# keyboardV0_1.net
KiCad netlist of a schematic drawn in Altium Designer
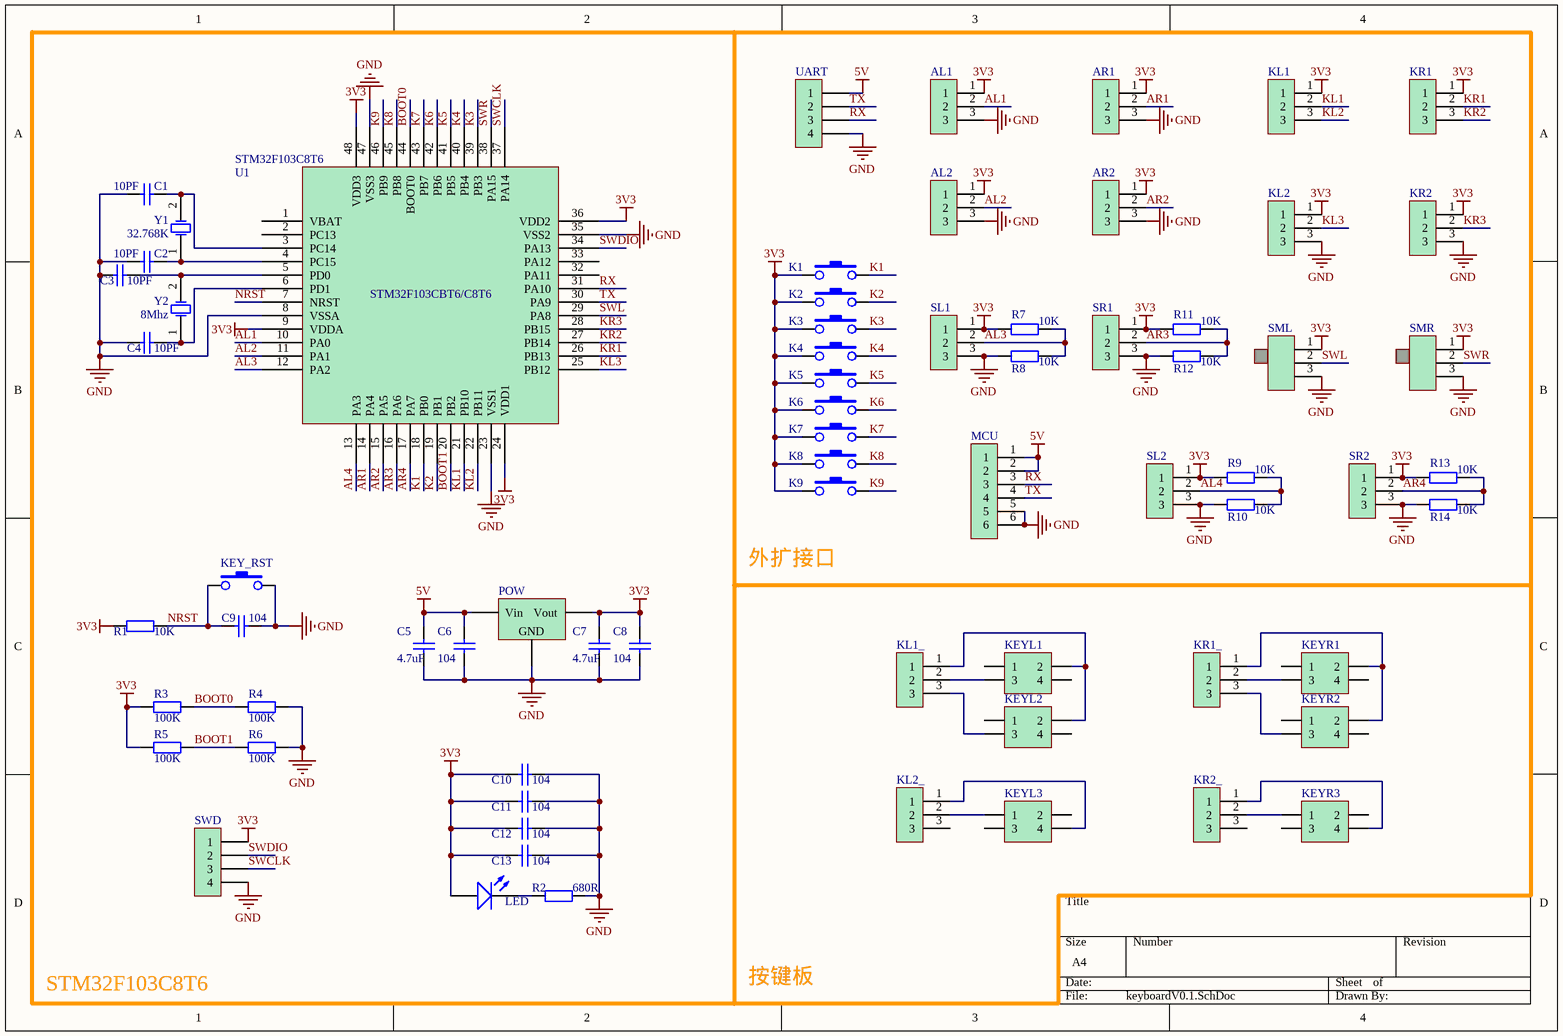
[diagram p0: keyboardV0.1.SchDoc]

(export (version "E")
  (design (tool "Eeschema 10.0.6"))
  (components
    (comp (ref "AL1")
      (value "SH1.25mm_3P")
      (footprint "SH1.25mm_3P")
      (libsource (lib "MT_Connector") (part "SH1.25mm_3P"))
    )
    (comp (ref "AL2")
      (value "SH1.25mm_3P")
      (footprint "SH1.25mm_3P")
      (libsource (lib "MT_Connector") (part "SH1.25mm_3P"))
    )
    (comp (ref "AR1")
      (value "SH1.25mm_3P")
      (footprint "SH1.25mm_3P")
      (libsource (lib "MT_Connector") (part "SH1.25mm_3P"))
    )
    (comp (ref "AR2")
      (value "SH1.25mm_3P")
      (footprint "SH1.25mm_3P")
      (libsource (lib "MT_Connector") (part "SH1.25mm_3P"))
    )
    (comp (ref "C1") (value "10PF") (footprint "0603_C") (libsource (lib "MT_Device") (part "0603_CAP")))
    (comp (ref "C2") (value "10PF") (footprint "0603_C") (libsource (lib "MT_Device") (part "0603_CAP")))
    (comp (ref "C3") (value "10PF") (footprint "0603_C") (libsource (lib "MT_Device") (part "0603_CAP")))
    (comp (ref "C4") (value "10PF") (footprint "0603_C") (libsource (lib "MT_Device") (part "0603_CAP")))
    (comp (ref "C5") (value "4.7uF") (footprint "0603_C") (libsource (lib "MT_Device") (part "0603_CAP")))
    (comp (ref "C6") (value "104") (footprint "0603_C") (libsource (lib "MT_Device") (part "0603_CAP")))
    (comp (ref "C7") (value "4.7uF") (footprint "0603_C") (libsource (lib "MT_Device") (part "0603_CAP")))
    (comp (ref "C8") (value "104") (footprint "0603_C") (libsource (lib "MT_Device") (part "0603_CAP")))
    (comp (ref "C9") (value "104") (footprint "0603_C") (libsource (lib "MT_Device") (part "0603_CAP")))
    (comp (ref "C10") (value "104") (footprint "0603_C") (libsource (lib "MT_Device") (part "0603_CAP")))
    (comp (ref "C11") (value "104") (footprint "0603_C") (libsource (lib "MT_Device") (part "0603_CAP")))
    (comp (ref "C12") (value "104") (footprint "0603_C") (libsource (lib "MT_Device") (part "0603_CAP")))
    (comp (ref "C13") (value "104") (footprint "0603_C") (libsource (lib "MT_Device") (part "0603_CAP")))
    (comp (ref "K1")
      (value "KEY_S_6*6")
      (footprint "KEY_S_6*6")
      (libsource (lib "MT_Device") (part "KEY_S_6*6"))
    )
    (comp (ref "K2")
      (value "KEY_S_6*6")
      (footprint "KEY_S_6*6")
      (libsource (lib "MT_Device") (part "KEY_S_6*6"))
    )
    (comp (ref "K3")
      (value "KEY_S_6*6")
      (footprint "KEY_S_6*6")
      (libsource (lib "MT_Device") (part "KEY_S_6*6"))
    )
    (comp (ref "K4")
      (value "KEY_S_6*6")
      (footprint "KEY_S_6*6")
      (libsource (lib "MT_Device") (part "KEY_S_6*6"))
    )
    (comp (ref "K5")
      (value "KEY_S_6*6")
      (footprint "KEY_S_6*6")
      (libsource (lib "MT_Device") (part "KEY_S_6*6"))
    )
    (comp (ref "K6")
      (value "KEY_S_6*6")
      (footprint "KEY_S_6*6")
      (libsource (lib "MT_Device") (part "KEY_S_6*6"))
    )
    (comp (ref "K7")
      (value "KEY_S_6*6")
      (footprint "KEY_S_6*6")
      (libsource (lib "MT_Device") (part "KEY_S_6*6"))
    )
    (comp (ref "K8")
      (value "KEY_S_6*6")
      (footprint "KEY_S_6*6")
      (libsource (lib "MT_Device") (part "KEY_S_6*6"))
    )
    (comp (ref "K9")
      (value "KEY_S_6*6")
      (footprint "KEY_S_6*6")
      (libsource (lib "MT_Device") (part "KEY_S_6*6"))
    )
    (comp (ref "KEYL1") (value "KEY") (footprint "KEY_6*6") (libsource (lib "MT_Device") (part "KEY_6*6")))
    (comp (ref "KEYL2") (value "KEY") (footprint "KEY_6*6") (libsource (lib "MT_Device") (part "KEY_6*6")))
    (comp (ref "KEYL3") (value "KEY") (footprint "KEY_6*6") (libsource (lib "MT_Device") (part "KEY_6*6")))
    (comp (ref "KEYR1") (value "KEY") (footprint "KEY_6*6") (libsource (lib "MT_Device") (part "KEY_6*6")))
    (comp (ref "KEYR2") (value "KEY") (footprint "KEY_6*6") (libsource (lib "MT_Device") (part "KEY_6*6")))
    (comp (ref "KEYR3") (value "KEY") (footprint "KEY_6*6") (libsource (lib "MT_Device") (part "KEY_6*6")))
    (comp (ref "KEY_RST")
      (value "KEY_SMT")
      (footprint "KEY_SMT")
      (libsource (lib "MT_Device") (part "KEY_SMT"))
    )
    (comp (ref "KL1")
      (value "SH1.25mm_3P")
      (footprint "SH1.25mm_3P")
      (libsource (lib "MT_Connector") (part "SH1.25mm_3P"))
    )
    (comp (ref "KL1_")
      (value "SH1.25mm_3P")
      (footprint "SH1.25mm_3P")
      (libsource (lib "MT_Connector") (part "SH1.25mm_3P"))
    )
    (comp (ref "KL2")
      (value "SH1.25mm_3P")
      (footprint "SH1.25mm_3P")
      (libsource (lib "MT_Connector") (part "SH1.25mm_3P"))
    )
    (comp (ref "KL2_")
      (value "SH1.25mm_3P")
      (footprint "SH1.25mm_3P")
      (libsource (lib "MT_Connector") (part "SH1.25mm_3P"))
    )
    (comp (ref "KR1")
      (value "SH1.25mm_3P")
      (footprint "SH1.25mm_3P")
      (libsource (lib "MT_Connector") (part "SH1.25mm_3P"))
    )
    (comp (ref "KR1_")
      (value "SH1.25mm_3P")
      (footprint "SH1.25mm_3P")
      (libsource (lib "MT_Connector") (part "SH1.25mm_3P"))
    )
    (comp (ref "KR2")
      (value "SH1.25mm_3P")
      (footprint "SH1.25mm_3P")
      (libsource (lib "MT_Connector") (part "SH1.25mm_3P"))
    )
    (comp (ref "KR2_")
      (value "SH1.25mm_3P")
      (footprint "SH1.25mm_3P")
      (libsource (lib "MT_Connector") (part "SH1.25mm_3P"))
    )
    (comp (ref "LED")
      (value "0603_LED")
      (footprint "0603_LED")
      (libsource (lib "MT_Device") (part "0603_LED"))
    )
    (comp (ref "MCU")
      (value "SH1.25mm_6P")
      (footprint "SH1.25MM_6P")
      (libsource (lib "MT_Connector") (part "SH1.25mm_6P"))
    )
    (comp (ref "POW")
      (value "AMS1117_3.3")
      (footprint "SOT223")
      (libsource (lib "MT_Device") (part "AMS1117_3.3"))
    )
    (comp (ref "R1") (value "10K") (footprint "0603_R") (libsource (lib "") (part "0603_RES_1")))
    (comp (ref "R2") (value "680R") (footprint "0603_R") (libsource (lib "") (part "0603_RES_1")))
    (comp (ref "R3") (value "100K") (footprint "0603_R") (libsource (lib "MT_Device") (part "0603_RES")))
    (comp (ref "R4") (value "100K") (footprint "0603_R") (libsource (lib "MT_Device") (part "0603_RES")))
    (comp (ref "R5") (value "100K") (footprint "0603_R") (libsource (lib "MT_Device") (part "0603_RES")))
    (comp (ref "R6") (value "100K") (footprint "0603_R") (libsource (lib "MT_Device") (part "0603_RES")))
    (comp (ref "R7") (value "10K") (footprint "0603_R") (libsource (lib "MT_Device") (part "0603_RES")))
    (comp (ref "R8") (value "10K") (footprint "0603_R") (libsource (lib "MT_Device") (part "0603_RES")))
    (comp (ref "R9") (value "10K") (footprint "0603_R") (libsource (lib "MT_Device") (part "0603_RES")))
    (comp (ref "R10") (value "10K") (footprint "0603_R") (libsource (lib "MT_Device") (part "0603_RES")))
    (comp (ref "R11") (value "10K") (footprint "0603_R") (libsource (lib "MT_Device") (part "0603_RES")))
    (comp (ref "R12") (value "10K") (footprint "0603_R") (libsource (lib "MT_Device") (part "0603_RES")))
    (comp (ref "R13") (value "10K") (footprint "0603_R") (libsource (lib "MT_Device") (part "0603_RES")))
    (comp (ref "R14") (value "10K") (footprint "0603_R") (libsource (lib "MT_Device") (part "0603_RES")))
    (comp (ref "SL1")
      (value "SH1.25mm_3P")
      (footprint "SH1.25mm_3P")
      (libsource (lib "MT_Connector") (part "SH1.25mm_3P"))
    )
    (comp (ref "SL2")
      (value "SH1.25mm_3P")
      (footprint "SH1.25mm_3P")
      (libsource (lib "MT_Connector") (part "SH1.25mm_3P"))
    )
    (comp (ref "SML")
      (value "SWITCH")
      (footprint "SWITCH_SS12F44")
      (libsource (lib "MT_Device") (part "SWITCH_SS12F44"))
    )
    (comp (ref "SMR")
      (value "SWITCH")
      (footprint "SWITCH_SS12F44")
      (libsource (lib "MT_Device") (part "SWITCH_SS12F44"))
    )
    (comp (ref "SR1")
      (value "SH1.25mm_3P")
      (footprint "SH1.25mm_3P")
      (libsource (lib "MT_Connector") (part "SH1.25mm_3P"))
    )
    (comp (ref "SR2")
      (value "SH1.25mm_3P")
      (footprint "SH1.25mm_3P")
      (libsource (lib "MT_Connector") (part "SH1.25mm_3P"))
    )
    (comp (ref "SWD")
      (value "Header_2.54_4P")
      (footprint "HDR1_4P")
      (libsource (lib "MT_Connector") (part "Header_2.54_4P"))
    )
    (comp (ref "U1")
      (value "STM32F103C8T6")
      (footprint "LQFP48")
      (libsource (lib "MT_Chip") (part "STM32F103C8T6"))
    )
    (comp (ref "UART")
      (value "Header_2.54_4P")
      (footprint "HDR1_4P")
      (libsource (lib "MT_Connector") (part "Header_2.54_4P"))
    )
    (comp (ref "Y1")
      (value "32.768K")
      (footprint "XTAL_32.768_3215_2")
      (libsource (lib "MT_Device") (part "XTAL_32.768_3215_2"))
    )
    (comp (ref "Y2")
      (value "8Mhz")
      (footprint "XTAL_5032_2")
      (libsource (lib "MT_Device") (part "XTAL_8MHz_5032_2"))
    )
  )
  (nets
    (net (code "1") (name "/AL1") (class "Default")
      (node (ref "AL1") (pin "2") (pinfunction "2_2") (pintype "passive"))
      (node (ref "U1") (pin "10") (pinfunction "PA0_10") (pintype "passive"))
    )
    (net (code "2") (name "/AL2") (class "Default")
      (node (ref "AL2") (pin "2") (pinfunction "2_2") (pintype "passive"))
      (node (ref "U1") (pin "11") (pinfunction "PA1_11") (pintype "passive"))
    )
    (net (code "3") (name "/AL3") (class "Default")
      (node (ref "R7") (pin "1") (pinfunction "1_1") (pintype "passive"))
      (node (ref "R8") (pin "1") (pinfunction "1_1") (pintype "passive"))
      (node (ref "SL1") (pin "2") (pinfunction "2_2") (pintype "passive"))
      (node (ref "U1") (pin "12") (pinfunction "PA2_12") (pintype "passive"))
    )
    (net (code "4") (name "/AL4") (class "Default")
      (node (ref "R10") (pin "1") (pinfunction "1_1") (pintype "passive"))
      (node (ref "R9") (pin "1") (pinfunction "1_1") (pintype "passive"))
      (node (ref "SL2") (pin "2") (pinfunction "2_2") (pintype "passive"))
      (node (ref "U1") (pin "13") (pinfunction "PA3_13") (pintype "passive"))
    )
    (net (code "5") (name "/AR1") (class "Default")
      (node (ref "AR1") (pin "2") (pinfunction "2_2") (pintype "passive"))
      (node (ref "U1") (pin "14") (pinfunction "PA4_14") (pintype "passive"))
    )
    (net (code "6") (name "/AR2") (class "Default")
      (node (ref "AR2") (pin "2") (pinfunction "2_2") (pintype "passive"))
      (node (ref "U1") (pin "15") (pinfunction "PA5_15") (pintype "passive"))
    )
    (net (code "7") (name "/AR3") (class "Default")
      (node (ref "R11") (pin "1") (pinfunction "1_1") (pintype "passive"))
      (node (ref "R12") (pin "1") (pinfunction "1_1") (pintype "passive"))
      (node (ref "SR1") (pin "2") (pinfunction "2_2") (pintype "passive"))
      (node (ref "U1") (pin "16") (pinfunction "PA6_16") (pintype "passive"))
    )
    (net (code "8") (name "/AR4") (class "Default")
      (node (ref "R13") (pin "1") (pinfunction "1_1") (pintype "passive"))
      (node (ref "R14") (pin "1") (pinfunction "1_1") (pintype "passive"))
      (node (ref "SR2") (pin "2") (pinfunction "2_2") (pintype "passive"))
      (node (ref "U1") (pin "17") (pinfunction "PA7_17") (pintype "passive"))
    )
    (net (code "9") (name "/BOOT0") (class "Default")
      (node (ref "R3") (pin "1") (pinfunction "1_1") (pintype "passive"))
      (node (ref "R4") (pin "2") (pinfunction "2_2") (pintype "passive"))
      (node (ref "U1") (pin "44") (pinfunction "BOOT0_44") (pintype "passive"))
    )
    (net (code "10") (name "/BOOT1") (class "Default")
      (node (ref "R5") (pin "1") (pinfunction "1_1") (pintype "passive"))
      (node (ref "R6") (pin "2") (pinfunction "2_2") (pintype "passive"))
      (node (ref "U1") (pin "20") (pinfunction "PB2_20") (pintype "passive"))
    )
    (net (code "11") (name "/K1") (class "Default")
      (node (ref "K1") (pin "2") (pinfunction "2_2") (pintype "passive"))
      (node (ref "U1") (pin "18") (pinfunction "PB0_18") (pintype "passive"))
    )
    (net (code "12") (name "/K2") (class "Default")
      (node (ref "K2") (pin "2") (pinfunction "2_2") (pintype "passive"))
      (node (ref "U1") (pin "19") (pinfunction "PB1_19") (pintype "passive"))
    )
    (net (code "13") (name "/K3") (class "Default")
      (node (ref "K3") (pin "2") (pinfunction "2_2") (pintype "passive"))
      (node (ref "U1") (pin "39") (pinfunction "PB3_39") (pintype "passive"))
    )
    (net (code "14") (name "/K4") (class "Default")
      (node (ref "K4") (pin "2") (pinfunction "2_2") (pintype "passive"))
      (node (ref "U1") (pin "40") (pinfunction "PB4_40") (pintype "passive"))
    )
    (net (code "15") (name "/K5") (class "Default")
      (node (ref "K5") (pin "2") (pinfunction "2_2") (pintype "passive"))
      (node (ref "U1") (pin "41") (pinfunction "PB5_41") (pintype "passive"))
    )
    (net (code "16") (name "/K6") (class "Default")
      (node (ref "K6") (pin "2") (pinfunction "2_2") (pintype "passive"))
      (node (ref "U1") (pin "42") (pinfunction "PB6_42") (pintype "passive"))
    )
    (net (code "17") (name "/K7") (class "Default")
      (node (ref "K7") (pin "2") (pinfunction "2_2") (pintype "passive"))
      (node (ref "U1") (pin "43") (pinfunction "PB7_43") (pintype "passive"))
    )
    (net (code "18") (name "/K8") (class "Default")
      (node (ref "K8") (pin "2") (pinfunction "2_2") (pintype "passive"))
      (node (ref "U1") (pin "45") (pinfunction "PB8_45") (pintype "passive"))
    )
    (net (code "19") (name "/K9") (class "Default")
      (node (ref "K9") (pin "2") (pinfunction "2_2") (pintype "passive"))
      (node (ref "U1") (pin "46") (pinfunction "PB9_46") (pintype "passive"))
    )
    (net (code "20") (name "/KL1") (class "Default")
      (node (ref "KL1") (pin "2") (pinfunction "2_2") (pintype "passive"))
      (node (ref "U1") (pin "21") (pinfunction "PB10_21") (pintype "passive"))
    )
    (net (code "21") (name "/KL2") (class "Default")
      (node (ref "KL1") (pin "3") (pinfunction "3_3") (pintype "passive"))
      (node (ref "U1") (pin "22") (pinfunction "PB11_22") (pintype "passive"))
    )
    (net (code "22") (name "/KL3") (class "Default")
      (node (ref "KL2") (pin "2") (pinfunction "2_2") (pintype "passive"))
      (node (ref "U1") (pin "25") (pinfunction "PB12_25") (pintype "passive"))
    )
    (net (code "23") (name "/KR1") (class "Default")
      (node (ref "KR1") (pin "2") (pinfunction "2_2") (pintype "passive"))
      (node (ref "U1") (pin "26") (pinfunction "PB13_26") (pintype "passive"))
    )
    (net (code "24") (name "/KR2") (class "Default")
      (node (ref "KR1") (pin "3") (pinfunction "3_3") (pintype "passive"))
      (node (ref "U1") (pin "27") (pinfunction "PB14_27") (pintype "passive"))
    )
    (net (code "25") (name "/KR3") (class "Default")
      (node (ref "KR2") (pin "2") (pinfunction "2_2") (pintype "passive"))
      (node (ref "U1") (pin "28") (pinfunction "PB15_28") (pintype "passive"))
    )
    (net (code "26") (name "/NRST") (class "Default")
      (node (ref "C9") (pin "2") (pinfunction "2_2") (pintype "passive"))
      (node (ref "KEY_RST") (pin "1") (pinfunction "1_1") (pintype "passive"))
      (node (ref "R1") (pin "2") (pinfunction "2_2") (pintype "passive"))
      (node (ref "U1") (pin "7") (pinfunction "NRST_7") (pintype "passive"))
    )
    (net (code "27") (name "/RX") (class "Default")
      (node (ref "MCU") (pin "3") (pinfunction "3_3") (pintype "passive"))
      (node (ref "U1") (pin "31") (pinfunction "PA10_31") (pintype "passive"))
      (node (ref "UART") (pin "3") (pinfunction "3_3") (pintype "passive"))
    )
    (net (code "28") (name "/SWCLK") (class "Default")
      (node (ref "SWD") (pin "3") (pinfunction "3_3") (pintype "passive"))
      (node (ref "U1") (pin "37") (pinfunction "PA14_37") (pintype "passive"))
    )
    (net (code "29") (name "/SWDIO") (class "Default")
      (node (ref "SWD") (pin "2") (pinfunction "2_2") (pintype "passive"))
      (node (ref "U1") (pin "34") (pinfunction "PA13_34") (pintype "passive"))
    )
    (net (code "30") (name "/SWL") (class "Default")
      (node (ref "SML") (pin "2") (pinfunction "2_2") (pintype "passive"))
      (node (ref "U1") (pin "29") (pinfunction "PA8_29") (pintype "passive"))
    )
    (net (code "31") (name "/SWR") (class "Default")
      (node (ref "SMR") (pin "2") (pinfunction "2_2") (pintype "passive"))
      (node (ref "U1") (pin "38") (pinfunction "PA15_38") (pintype "passive"))
    )
    (net (code "32") (name "/TX") (class "Default")
      (node (ref "MCU") (pin "4") (pinfunction "4_4") (pintype "passive"))
      (node (ref "U1") (pin "30") (pinfunction "PA9_30") (pintype "passive"))
      (node (ref "UART") (pin "2") (pinfunction "2_2") (pintype "passive"))
    )
    (net (code "33") (name "3V3") (class "Default")
      (node (ref "AL1") (pin "1") (pinfunction "1_1") (pintype "passive"))
      (node (ref "AL2") (pin "1") (pinfunction "1_1") (pintype "passive"))
      (node (ref "AR1") (pin "1") (pinfunction "1_1") (pintype "passive"))
      (node (ref "AR2") (pin "1") (pinfunction "1_1") (pintype "passive"))
      (node (ref "C10") (pin "2") (pinfunction "2_2") (pintype "passive"))
      (node (ref "C11") (pin "2") (pinfunction "2_2") (pintype "passive"))
      (node (ref "C12") (pin "2") (pinfunction "2_2") (pintype "passive"))
      (node (ref "C13") (pin "2") (pinfunction "2_2") (pintype "passive"))
      (node (ref "C7") (pin "1") (pinfunction "1_1") (pintype "passive"))
      (node (ref "C8") (pin "1") (pinfunction "1_1") (pintype "passive"))
      (node (ref "K1") (pin "1") (pinfunction "1_1") (pintype "passive"))
      (node (ref "K2") (pin "1") (pinfunction "1_1") (pintype "passive"))
      (node (ref "K3") (pin "1") (pinfunction "1_1") (pintype "passive"))
      (node (ref "K4") (pin "1") (pinfunction "1_1") (pintype "passive"))
      (node (ref "K5") (pin "1") (pinfunction "1_1") (pintype "passive"))
      (node (ref "K6") (pin "1") (pinfunction "1_1") (pintype "passive"))
      (node (ref "K7") (pin "1") (pinfunction "1_1") (pintype "passive"))
      (node (ref "K8") (pin "1") (pinfunction "1_1") (pintype "passive"))
      (node (ref "K9") (pin "1") (pinfunction "1_1") (pintype "passive"))
      (node (ref "KL1") (pin "1") (pinfunction "1_1") (pintype "passive"))
      (node (ref "KL2") (pin "1") (pinfunction "1_1") (pintype "passive"))
      (node (ref "KR1") (pin "1") (pinfunction "1_1") (pintype "passive"))
      (node (ref "KR2") (pin "1") (pinfunction "1_1") (pintype "passive"))
      (node (ref "LED") (pin "A") (pinfunction "A_A") (pintype "passive"))
      (node (ref "POW") (pin "2") (pinfunction "Vout_2") (pintype "passive"))
      (node (ref "R1") (pin "1") (pinfunction "1_1") (pintype "passive"))
      (node (ref "R11") (pin "2") (pinfunction "2_2") (pintype "passive"))
      (node (ref "R13") (pin "2") (pinfunction "2_2") (pintype "passive"))
      (node (ref "R3") (pin "2") (pinfunction "2_2") (pintype "passive"))
      (node (ref "R5") (pin "2") (pinfunction "2_2") (pintype "passive"))
      (node (ref "R7") (pin "2") (pinfunction "2_2") (pintype "passive"))
      (node (ref "R9") (pin "2") (pinfunction "2_2") (pintype "passive"))
      (node (ref "SL1") (pin "1") (pinfunction "1_1") (pintype "passive"))
      (node (ref "SL2") (pin "1") (pinfunction "1_1") (pintype "passive"))
      (node (ref "SML") (pin "1") (pinfunction "1_1") (pintype "passive"))
      (node (ref "SMR") (pin "1") (pinfunction "1_1") (pintype "passive"))
      (node (ref "SR1") (pin "1") (pinfunction "1_1") (pintype "passive"))
      (node (ref "SR2") (pin "1") (pinfunction "1_1") (pintype "passive"))
      (node (ref "SWD") (pin "1") (pinfunction "1_1") (pintype "passive"))
      (node (ref "U1") (pin "24") (pinfunction "VDD1_24") (pintype "passive"))
      (node (ref "U1") (pin "36") (pinfunction "VDD2_36") (pintype "passive"))
      (node (ref "U1") (pin "48") (pinfunction "VDD3_48") (pintype "passive"))
      (node (ref "U1") (pin "9") (pinfunction "VDDA_9") (pintype "passive"))
    )
    (net (code "34") (name "5V") (class "Default")
      (node (ref "C5") (pin "1") (pinfunction "1_1") (pintype "passive"))
      (node (ref "C6") (pin "1") (pinfunction "1_1") (pintype "passive"))
      (node (ref "MCU") (pin "1") (pinfunction "1_1") (pintype "passive"))
      (node (ref "MCU") (pin "2") (pinfunction "2_2") (pintype "passive"))
      (node (ref "POW") (pin "3") (pinfunction "Vin_3") (pintype "passive"))
      (node (ref "UART") (pin "1") (pinfunction "1_1") (pintype "passive"))
    )
    (net (code "35") (name "GND") (class "Default")
      (node (ref "AL1") (pin "3") (pinfunction "3_3") (pintype "passive"))
      (node (ref "AL2") (pin "3") (pinfunction "3_3") (pintype "passive"))
      (node (ref "AR1") (pin "3") (pinfunction "3_3") (pintype "passive"))
      (node (ref "AR2") (pin "3") (pinfunction "3_3") (pintype "passive"))
      (node (ref "C1") (pin "1") (pinfunction "1_1") (pintype "passive"))
      (node (ref "C10") (pin "1") (pinfunction "1_1") (pintype "passive"))
      (node (ref "C11") (pin "1") (pinfunction "1_1") (pintype "passive"))
      (node (ref "C12") (pin "1") (pinfunction "1_1") (pintype "passive"))
      (node (ref "C13") (pin "1") (pinfunction "1_1") (pintype "passive"))
      (node (ref "C2") (pin "1") (pinfunction "1_1") (pintype "passive"))
      (node (ref "C3") (pin "1") (pinfunction "1_1") (pintype "passive"))
      (node (ref "C4") (pin "1") (pinfunction "1_1") (pintype "passive"))
      (node (ref "C5") (pin "2") (pinfunction "2_2") (pintype "passive"))
      (node (ref "C6") (pin "2") (pinfunction "2_2") (pintype "passive"))
      (node (ref "C7") (pin "2") (pinfunction "2_2") (pintype "passive"))
      (node (ref "C8") (pin "2") (pinfunction "2_2") (pintype "passive"))
      (node (ref "C9") (pin "1") (pinfunction "1_1") (pintype "passive"))
      (node (ref "KEY_RST") (pin "2") (pinfunction "2_2") (pintype "passive"))
      (node (ref "KL2") (pin "3") (pinfunction "3_3") (pintype "passive"))
      (node (ref "KR2") (pin "3") (pinfunction "3_3") (pintype "passive"))
      (node (ref "MCU") (pin "5") (pinfunction "5_5") (pintype "passive"))
      (node (ref "MCU") (pin "6") (pinfunction "6_6") (pintype "passive"))
      (node (ref "POW") (pin "1") (pinfunction "GND_1") (pintype "passive"))
      (node (ref "R10") (pin "2") (pinfunction "2_2") (pintype "passive"))
      (node (ref "R12") (pin "2") (pinfunction "2_2") (pintype "passive"))
      (node (ref "R14") (pin "2") (pinfunction "2_2") (pintype "passive"))
      (node (ref "R2") (pin "2") (pinfunction "2_2") (pintype "passive"))
      (node (ref "R4") (pin "1") (pinfunction "1_1") (pintype "passive"))
      (node (ref "R6") (pin "1") (pinfunction "1_1") (pintype "passive"))
      (node (ref "R8") (pin "2") (pinfunction "2_2") (pintype "passive"))
      (node (ref "SL1") (pin "3") (pinfunction "3_3") (pintype "passive"))
      (node (ref "SL2") (pin "3") (pinfunction "3_3") (pintype "passive"))
      (node (ref "SML") (pin "3") (pinfunction "3_3") (pintype "passive"))
      (node (ref "SMR") (pin "3") (pinfunction "3_3") (pintype "passive"))
      (node (ref "SR1") (pin "3") (pinfunction "3_3") (pintype "passive"))
      (node (ref "SR2") (pin "3") (pinfunction "3_3") (pintype "passive"))
      (node (ref "SWD") (pin "4") (pinfunction "4_4") (pintype "passive"))
      (node (ref "U1") (pin "23") (pinfunction "VSS1_23") (pintype "passive"))
      (node (ref "U1") (pin "35") (pinfunction "VSS2_35") (pintype "passive"))
      (node (ref "U1") (pin "47") (pinfunction "VSS3_47") (pintype "passive"))
      (node (ref "U1") (pin "8") (pinfunction "VSSA_8") (pintype "passive"))
      (node (ref "UART") (pin "4") (pinfunction "4_4") (pintype "passive"))
    )
    (net (code "36") (name "Net-(KEYL1-Pad2)") (class "Default")
      (node (ref "KEYL1") (pin "2") (pinfunction "2_2") (pintype "passive"))
      (node (ref "KEYL2") (pin "2") (pinfunction "2_2") (pintype "passive"))
      (node (ref "KL1_") (pin "1") (pinfunction "1_1") (pintype "passive"))
    )
    (net (code "37") (name "Net-(KEYL1-Pad3)") (class "Default")
      (node (ref "KEYL1") (pin "3") (pinfunction "3_3") (pintype "passive"))
      (node (ref "KL1_") (pin "2") (pinfunction "2_2") (pintype "passive"))
    )
    (net (code "38") (name "Net-(KEYL2-Pad3)") (class "Default")
      (node (ref "KEYL2") (pin "3") (pinfunction "3_3") (pintype "passive"))
      (node (ref "KL1_") (pin "3") (pinfunction "3_3") (pintype "passive"))
    )
    (net (code "39") (name "Net-(KEYL3-Pad1)") (class "Default")
      (node (ref "KEYL3") (pin "1") (pinfunction "1_1") (pintype "passive"))
      (node (ref "KL2_") (pin "2") (pinfunction "2_2") (pintype "passive"))
    )
    (net (code "40") (name "Net-(KEYL3-Pad4)") (class "Default")
      (node (ref "KEYL3") (pin "4") (pinfunction "4_4") (pintype "passive"))
      (node (ref "KL2_") (pin "1") (pinfunction "1_1") (pintype "passive"))
    )
    (net (code "41") (name "Net-(KEYR1-Pad2)") (class "Default")
      (node (ref "KEYR1") (pin "2") (pinfunction "2_2") (pintype "passive"))
      (node (ref "KEYR2") (pin "2") (pinfunction "2_2") (pintype "passive"))
      (node (ref "KR1_") (pin "1") (pinfunction "1_1") (pintype "passive"))
    )
    (net (code "42") (name "Net-(KEYR1-Pad3)") (class "Default")
      (node (ref "KEYR1") (pin "3") (pinfunction "3_3") (pintype "passive"))
      (node (ref "KR1_") (pin "2") (pinfunction "2_2") (pintype "passive"))
    )
    (net (code "43") (name "Net-(KEYR2-Pad3)") (class "Default")
      (node (ref "KEYR2") (pin "3") (pinfunction "3_3") (pintype "passive"))
      (node (ref "KR1_") (pin "3") (pinfunction "3_3") (pintype "passive"))
    )
    (net (code "44") (name "Net-(KEYR3-Pad1)") (class "Default")
      (node (ref "KEYR3") (pin "1") (pinfunction "1_1") (pintype "passive"))
      (node (ref "KR2_") (pin "2") (pinfunction "2_2") (pintype "passive"))
    )
    (net (code "45") (name "Net-(KEYR3-Pad4)") (class "Default")
      (node (ref "KEYR3") (pin "4") (pinfunction "4_4") (pintype "passive"))
      (node (ref "KR2_") (pin "1") (pinfunction "1_1") (pintype "passive"))
    )
    (net (code "46") (name "Net-(LED-PadK)") (class "Default")
      (node (ref "LED") (pin "K") (pinfunction "K_K") (pintype "passive"))
      (node (ref "R2") (pin "1") (pinfunction "1_1") (pintype "passive"))
    )
    (net (code "47") (name "Net-(U1-PC14)") (class "Default")
      (node (ref "C1") (pin "2") (pinfunction "2_2") (pintype "passive"))
      (node (ref "U1") (pin "3") (pinfunction "PC14_3") (pintype "passive"))
      (node (ref "Y1") (pin "2") (pinfunction "OSC2_2") (pintype "passive"))
    )
    (net (code "48") (name "Net-(U1-PC15)") (class "Default")
      (node (ref "C2") (pin "2") (pinfunction "2_2") (pintype "passive"))
      (node (ref "U1") (pin "4") (pinfunction "PC15_4") (pintype "passive"))
      (node (ref "Y1") (pin "1") (pinfunction "OSC1_1") (pintype "passive"))
    )
    (net (code "49") (name "Net-(U1-PD0)") (class "Default")
      (node (ref "C3") (pin "2") (pinfunction "2_2") (pintype "passive"))
      (node (ref "U1") (pin "5") (pinfunction "PD0_5") (pintype "passive"))
      (node (ref "Y2") (pin "2") (pinfunction "OSC2_2") (pintype "passive"))
    )
    (net (code "50") (name "Net-(U1-PD1)") (class "Default")
      (node (ref "C4") (pin "2") (pinfunction "2_2") (pintype "passive"))
      (node (ref "U1") (pin "6") (pinfunction "PD1_6") (pintype "passive"))
      (node (ref "Y2") (pin "1") (pinfunction "OSC1_1") (pintype "passive"))
    )
    (net (code "51") (name "unconnected-(KEYL1-Pad1)") (class "Default")
      (node (ref "KEYL1") (pin "1") (pinfunction "1_1") (pintype "passive"))
    )
    (net (code "52") (name "unconnected-(KEYL1-Pad4)") (class "Default")
      (node (ref "KEYL1") (pin "4") (pinfunction "4_4") (pintype "passive"))
    )
    (net (code "53") (name "unconnected-(KEYL2-Pad1)") (class "Default")
      (node (ref "KEYL2") (pin "1") (pinfunction "1_1") (pintype "passive"))
    )
    (net (code "54") (name "unconnected-(KEYL2-Pad4)") (class "Default")
      (node (ref "KEYL2") (pin "4") (pinfunction "4_4") (pintype "passive"))
    )
    (net (code "55") (name "unconnected-(KEYL3-Pad2)") (class "Default")
      (node (ref "KEYL3") (pin "2") (pinfunction "2_2") (pintype "passive"))
    )
    (net (code "56") (name "unconnected-(KEYL3-Pad3)") (class "Default")
      (node (ref "KEYL3") (pin "3") (pinfunction "3_3") (pintype "passive"))
    )
    (net (code "57") (name "unconnected-(KEYR1-Pad1)") (class "Default")
      (node (ref "KEYR1") (pin "1") (pinfunction "1_1") (pintype "passive"))
    )
    (net (code "58") (name "unconnected-(KEYR1-Pad4)") (class "Default")
      (node (ref "KEYR1") (pin "4") (pinfunction "4_4") (pintype "passive"))
    )
    (net (code "59") (name "unconnected-(KEYR2-Pad1)") (class "Default")
      (node (ref "KEYR2") (pin "1") (pinfunction "1_1") (pintype "passive"))
    )
    (net (code "60") (name "unconnected-(KEYR2-Pad4)") (class "Default")
      (node (ref "KEYR2") (pin "4") (pinfunction "4_4") (pintype "passive"))
    )
    (net (code "61") (name "unconnected-(KEYR3-Pad2)") (class "Default")
      (node (ref "KEYR3") (pin "2") (pinfunction "2_2") (pintype "passive"))
    )
    (net (code "62") (name "unconnected-(KEYR3-Pad3)") (class "Default")
      (node (ref "KEYR3") (pin "3") (pinfunction "3_3") (pintype "passive"))
    )
    (net (code "63") (name "unconnected-(KL2_-Pad3)") (class "Default")
      (node (ref "KL2_") (pin "3") (pinfunction "3_3") (pintype "passive"))
    )
    (net (code "64") (name "unconnected-(KR2_-Pad3)") (class "Default")
      (node (ref "KR2_") (pin "3") (pinfunction "3_3") (pintype "passive"))
    )
    (net (code "65") (name "unconnected-(U1-PA11-Pad32)") (class "Default")
      (node (ref "U1") (pin "32") (pinfunction "PA11_32") (pintype "passive"))
    )
    (net (code "66") (name "unconnected-(U1-PA12-Pad33)") (class "Default")
      (node (ref "U1") (pin "33") (pinfunction "PA12_33") (pintype "passive"))
    )
    (net (code "67") (name "unconnected-(U1-PC13-Pad2)") (class "Default")
      (node (ref "U1") (pin "2") (pinfunction "PC13_2") (pintype "passive"))
    )
    (net (code "68") (name "unconnected-(U1-VBAT-Pad1)") (class "Default")
      (node (ref "U1") (pin "1") (pinfunction "VBAT_1") (pintype "passive"))
    )
  )
)
